# PM_proto_3.net
KiCad netlist of a schematic drawn in EAGLE
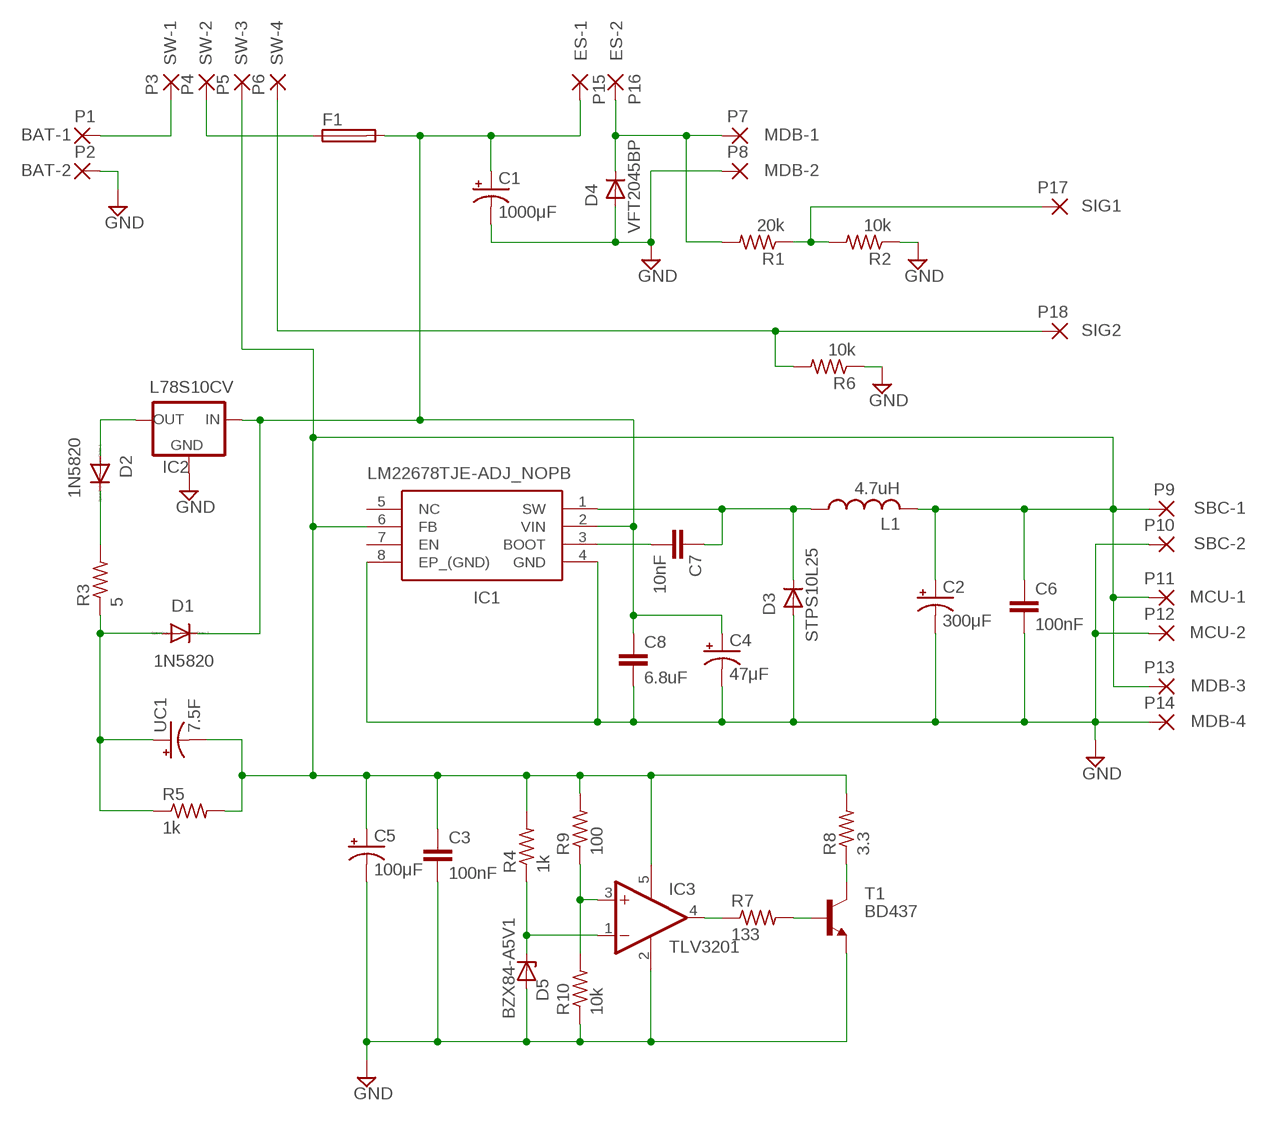
[diagram p0: schematic, sheet 1]

(export (version "E")
  (design (tool "Eeschema 10.0.6"))
  (components
    (comp (ref "C1")
      (value "1000μF")
      (footprint "eagle-import:E7,5-16")
      (libsource (lib "eagle-import") (part "CPOL-USE7.5-16"))
    )
    (comp (ref "C2")
      (value "300μF")
      (footprint "eagle-import:E2,5-6E")
      (libsource (lib "eagle-import") (part "CPOL-USE2,5-6E"))
    )
    (comp (ref "C3")
      (value "100nF")
      (footprint "eagle-import:C025-024X044")
      (libsource (lib "eagle-import") (part "C-EU025-024X044"))
    )
    (comp (ref "C4")
      (value "47μF")
      (footprint "eagle-import:E2,5-6E")
      (libsource (lib "eagle-import") (part "CPOL-USE2,5-6E"))
    )
    (comp (ref "C5")
      (value "100μF")
      (footprint "eagle-import:E2,5-6E")
      (libsource (lib "eagle-import") (part "CPOL-USE2,5-6E"))
    )
    (comp (ref "C6")
      (value "100nF")
      (footprint "eagle-import:C025-024X044")
      (libsource (lib "eagle-import") (part "C-EU025-024X044"))
    )
    (comp (ref "C7")
      (value "10nF")
      (footprint "eagle-import:C025-024X044")
      (libsource (lib "eagle-import") (part "C-EU025-024X044"))
    )
    (comp (ref "C8")
      (value "6.8uF")
      (footprint "eagle-import:C025-024X044")
      (libsource (lib "eagle-import") (part "C-EU025-024X044"))
    )
    (comp (ref "D1")
      (value "1N5820")
      (footprint "eagle-import:DO41-10")
      (libsource (lib "eagle-import") (part "1N4004"))
    )
    (comp (ref "D2")
      (value "1N5820")
      (footprint "eagle-import:DO41-10")
      (libsource (lib "eagle-import") (part "1N4004"))
    )
    (comp (ref "D3")
      (value "STPS10L25")
      (footprint "eagle-import:VFT2045BP")
      (libsource (lib "eagle-import") (part "VFT2045BP"))
    )
    (comp (ref "D4")
      (value "VFT2045BP")
      (footprint "eagle-import:VFT2045BP")
      (libsource (lib "eagle-import") (part "VFT2045BP"))
    )
    (comp (ref "D5")
      (value "BZX84-A5V1")
      (footprint "eagle-import:DO41Z10")
      (libsource (lib "eagle-import") (part "1N4728"))
    )
    (comp (ref "F1")
      (value "0297015FUSE")
      (footprint "eagle-import:0297015HOLDER")
      (libsource (lib "eagle-import") (part "0297015FUSE"))
    )
    (comp (ref "IC1")
      (value "LM22678TJE-ADJ_NOPB")
      (footprint "eagle-import:LM22678TJEADJNOPB")
      (fields
        (field (name "ARROW_PART_NUMBER") "LM22678TJE-ADJ/NOPB")
        (field (name "RS_PART_NUMBER") "1625056")
      )
      (libsource (lib "eagle-import") (part "LM22678TJE-ADJ_NOPB"))
    )
    (comp (ref "IC2")
      (value "L78S10CV")
      (footprint "eagle-import:78XXS")
      (libsource (lib "eagle-import") (part "78XXS"))
    )
    (comp (ref "IC3")
      (value "TLV3201")
      (footprint "eagle-import:DBV-R-PDSO-G5")
      (libsource (lib "eagle-import") (part "TL331"))
    )
    (comp (ref "L1")
      (value "4.7uH")
      (footprint "eagle-import:6000-XXXX-RC")
      (libsource (lib "eagle-import") (part "L-US6000-XXX-RC"))
    )
    (comp (ref "P1")
      (value "BAT-1")
      (footprint "eagle-import:1,6_0,8")
      (libsource (lib "eagle-import") (part "1,6/0,8"))
    )
    (comp (ref "P2")
      (value "BAT-2")
      (footprint "eagle-import:1,6_0,8")
      (libsource (lib "eagle-import") (part "1,6/0,8"))
    )
    (comp (ref "P3")
      (value "SW-1")
      (footprint "eagle-import:1,6_0,8")
      (libsource (lib "eagle-import") (part "1,6/0,8"))
    )
    (comp (ref "P4")
      (value "SW-2")
      (footprint "eagle-import:1,6_0,8")
      (libsource (lib "eagle-import") (part "1,6/0,8"))
    )
    (comp (ref "P5")
      (value "SW-3")
      (footprint "eagle-import:1,6_0,8")
      (libsource (lib "eagle-import") (part "1,6/0,8"))
    )
    (comp (ref "P6")
      (value "SW-4")
      (footprint "eagle-import:1,6_0,8")
      (libsource (lib "eagle-import") (part "1,6/0,8"))
    )
    (comp (ref "P7")
      (value "MDB-1")
      (footprint "eagle-import:1,6_0,8")
      (libsource (lib "eagle-import") (part "1,6/0,8"))
    )
    (comp (ref "P8")
      (value "MDB-2")
      (footprint "eagle-import:1,6_0,8")
      (libsource (lib "eagle-import") (part "1,6/0,8"))
    )
    (comp (ref "P9")
      (value "SBC-1")
      (footprint "eagle-import:1,6_0,8")
      (libsource (lib "eagle-import") (part "1,6/0,8"))
    )
    (comp (ref "P10")
      (value "SBC-2")
      (footprint "eagle-import:1,6_0,8")
      (libsource (lib "eagle-import") (part "1,6/0,8"))
    )
    (comp (ref "P11")
      (value "MCU-1")
      (footprint "eagle-import:1,6_0,8")
      (libsource (lib "eagle-import") (part "1,6/0,8"))
    )
    (comp (ref "P12")
      (value "MCU-2")
      (footprint "eagle-import:1,6_0,8")
      (libsource (lib "eagle-import") (part "1,6/0,8"))
    )
    (comp (ref "P13")
      (value "MDB-3")
      (footprint "eagle-import:1,6_0,8")
      (libsource (lib "eagle-import") (part "1,6/0,8"))
    )
    (comp (ref "P14")
      (value "MDB-4")
      (footprint "eagle-import:1,6_0,8")
      (libsource (lib "eagle-import") (part "1,6/0,8"))
    )
    (comp (ref "P15")
      (value "ES-1")
      (footprint "eagle-import:1,6_0,8")
      (libsource (lib "eagle-import") (part "1,6/0,8"))
    )
    (comp (ref "P16")
      (value "ES-2")
      (footprint "eagle-import:1,6_0,8")
      (libsource (lib "eagle-import") (part "1,6/0,8"))
    )
    (comp (ref "P17")
      (value "SIG1")
      (footprint "eagle-import:1,6_0,8")
      (libsource (lib "eagle-import") (part "1,6/0,8"))
    )
    (comp (ref "P18")
      (value "SIG2")
      (footprint "eagle-import:1,6_0,8")
      (libsource (lib "eagle-import") (part "1,6/0,8"))
    )
    (comp (ref "R1")
      (value "20k")
      (footprint "eagle-import:0204_7")
      (libsource (lib "eagle-import") (part "R-US_0204/7"))
    )
    (comp (ref "R2")
      (value "10k")
      (footprint "eagle-import:0204_7")
      (libsource (lib "eagle-import") (part "R-US_0204/7"))
    )
    (comp (ref "R3")
      (value "5")
      (footprint "eagle-import:TNP10SC10R0FE")
      (libsource (lib "eagle-import") (part "TNP10SC10R0FE"))
    )
    (comp (ref "R4")
      (value "1k")
      (footprint "eagle-import:0204_7")
      (libsource (lib "eagle-import") (part "R-US_0204/7"))
    )
    (comp (ref "R5")
      (value "1k")
      (footprint "eagle-import:0204_7")
      (libsource (lib "eagle-import") (part "R-US_0204/7"))
    )
    (comp (ref "R6")
      (value "10k")
      (footprint "eagle-import:0204_7")
      (libsource (lib "eagle-import") (part "R-US_0204/7"))
    )
    (comp (ref "R7")
      (value "133")
      (footprint "eagle-import:0204_7")
      (libsource (lib "eagle-import") (part "R-US_0204/7"))
    )
    (comp (ref "R8")
      (value "3.3")
      (footprint "eagle-import:0204_7")
      (libsource (lib "eagle-import") (part "R-US_0204/7"))
    )
    (comp (ref "R9")
      (value "100")
      (footprint "eagle-import:0204_7")
      (libsource (lib "eagle-import") (part "R-US_0204/7"))
    )
    (comp (ref "R10")
      (value "10k")
      (footprint "eagle-import:0204_7")
      (libsource (lib "eagle-import") (part "R-US_0204/7"))
    )
    (comp (ref "T1")
      (value "BD437")
      (footprint "eagle-import:TO18")
      (libsource (lib "eagle-import") (part "2N706"))
    )
    (comp (ref "UC1")
      (value "7.5F")
      (footprint "eagle-import:SCMT32D755MRBB0")
      (libsource (lib "eagle-import") (part "SCMT32D755MRBB0"))
    )
  )
  (nets
    (net (code "1") (name "GND") (class "Default")
      (node (ref "C1") (pin "-") (pinfunction "-_-") (pintype "passive"))
      (node (ref "C2") (pin "-") (pinfunction "-_-") (pintype "passive"))
      (node (ref "C3") (pin "2") (pinfunction "2_2") (pintype "passive"))
      (node (ref "C4") (pin "-") (pinfunction "-_-") (pintype "passive"))
      (node (ref "C5") (pin "-") (pinfunction "-_-") (pintype "passive"))
      (node (ref "C6") (pin "2") (pinfunction "2_2") (pintype "passive"))
      (node (ref "C8") (pin "2") (pinfunction "2_2") (pintype "passive"))
      (node (ref "D3") (pin "2") (pinfunction "A_2") (pintype "passive"))
      (node (ref "D4") (pin "2") (pinfunction "A_2") (pintype "passive"))
      (node (ref "D5") (pin "A") (pinfunction "A_A") (pintype "passive"))
      (node (ref "IC1") (pin "4") (pinfunction "GND_4") (pintype "power_in"))
      (node (ref "IC1") (pin "8") (pinfunction "EP_(GND)_8") (pintype "power_in"))
      (node (ref "IC2") (pin "GND") (pinfunction "GND_GND") (pintype "input"))
      (node (ref "IC3") (pin "2") (pinfunction "GND_2") (pintype "power_in"))
      (node (ref "P10") (pin "1") (pinfunction "P_1") (pintype "passive"))
      (node (ref "P12") (pin "1") (pinfunction "P_1") (pintype "passive"))
      (node (ref "P14") (pin "1") (pinfunction "P_1") (pintype "passive"))
      (node (ref "P2") (pin "1") (pinfunction "P_1") (pintype "passive"))
      (node (ref "P8") (pin "1") (pinfunction "P_1") (pintype "passive"))
      (node (ref "R10") (pin "1") (pinfunction "1_1") (pintype "passive"))
      (node (ref "R2") (pin "1") (pinfunction "1_1") (pintype "passive"))
      (node (ref "R6") (pin "1") (pinfunction "1_1") (pintype "passive"))
      (node (ref "T1") (pin "1") (pinfunction "E_1") (pintype "passive"))
    )
    (net (code "2") (name "Net-(D2-PadA)") (class "Default")
      (node (ref "D2") (pin "A") (pinfunction "A_A") (pintype "passive"))
      (node (ref "IC2") (pin "OUT") (pinfunction "OUT_OUT") (pintype "passive"))
    )
    (net (code "3") (name "Net-(D2-PadC)") (class "Default")
      (node (ref "D2") (pin "C") (pinfunction "C_C") (pintype "passive"))
      (node (ref "R3") (pin "2") (pinfunction "2_2") (pintype "passive"))
    )
    (net (code "4") (name "Net-(D3-C)") (class "Default")
      (node (ref "C7") (pin "1") (pinfunction "1_1") (pintype "passive"))
      (node (ref "D3") (pin "1") (pinfunction "C_1") (pintype "passive"))
      (node (ref "IC1") (pin "1") (pinfunction "SW_1") (pintype "power_in"))
      (node (ref "L1") (pin "1") (pinfunction "1_1") (pintype "passive"))
    )
    (net (code "5") (name "Net-(D4-C)") (class "Default")
      (node (ref "D4") (pin "1") (pinfunction "C_1") (pintype "passive"))
      (node (ref "P16") (pin "1") (pinfunction "P_1") (pintype "passive"))
      (node (ref "P7") (pin "1") (pinfunction "P_1") (pintype "passive"))
      (node (ref "R1") (pin "2") (pinfunction "2_2") (pintype "passive"))
    )
    (net (code "6") (name "Net-(IC1-BOOT)") (class "Default")
      (node (ref "C7") (pin "2") (pinfunction "2_2") (pintype "passive"))
      (node (ref "IC1") (pin "3") (pinfunction "BOOT_3") (pintype "bidirectional"))
    )
    (net (code "7") (name "Net-(IC1-FB)") (class "Default")
      (node (ref "C2") (pin "+") (pinfunction "+_+") (pintype "passive"))
      (node (ref "C3") (pin "1") (pinfunction "1_1") (pintype "passive"))
      (node (ref "C5") (pin "+") (pinfunction "+_+") (pintype "passive"))
      (node (ref "C6") (pin "1") (pinfunction "1_1") (pintype "passive"))
      (node (ref "IC1") (pin "6") (pinfunction "FB_6") (pintype "input"))
      (node (ref "IC3") (pin "5") (pinfunction "V+_5") (pintype "power_in"))
      (node (ref "L1") (pin "2") (pinfunction "2_2") (pintype "passive"))
      (node (ref "P11") (pin "1") (pinfunction "P_1") (pintype "passive"))
      (node (ref "P13") (pin "1") (pinfunction "P_1") (pintype "passive"))
      (node (ref "P5") (pin "1") (pinfunction "P_1") (pintype "passive"))
      (node (ref "P9") (pin "1") (pinfunction "P_1") (pintype "passive"))
      (node (ref "R4") (pin "2") (pinfunction "2_2") (pintype "passive"))
      (node (ref "R5") (pin "2") (pinfunction "2_2") (pintype "passive"))
      (node (ref "R8") (pin "2") (pinfunction "2_2") (pintype "passive"))
      (node (ref "R9") (pin "2") (pinfunction "2_2") (pintype "passive"))
      (node (ref "UC1") (pin "2") (pinfunction "-_2") (pintype "passive"))
    )
    (net (code "8") (name "Net-(IC1-VIN)") (class "Default")
      (node (ref "C1") (pin "+") (pinfunction "+_+") (pintype "passive"))
      (node (ref "C4") (pin "+") (pinfunction "+_+") (pintype "passive"))
      (node (ref "C8") (pin "1") (pinfunction "1_1") (pintype "passive"))
      (node (ref "D1") (pin "C") (pinfunction "C_C") (pintype "passive"))
      (node (ref "F1") (pin "3") (pinfunction "2_3") (pintype "passive"))
      (node (ref "F1") (pin "4") (pinfunction "2_4") (pintype "passive"))
      (node (ref "IC1") (pin "2") (pinfunction "VIN_2") (pintype "power_in"))
      (node (ref "IC2") (pin "IN") (pinfunction "IN_IN") (pintype "input"))
      (node (ref "P15") (pin "1") (pinfunction "P_1") (pintype "passive"))
    )
    (net (code "9") (name "Net-(IC3-+IN)") (class "Default")
      (node (ref "IC3") (pin "3") (pinfunction "+IN_3") (pintype "input"))
      (node (ref "R10") (pin "2") (pinfunction "2_2") (pintype "passive"))
      (node (ref "R9") (pin "1") (pinfunction "1_1") (pintype "passive"))
    )
    (net (code "10") (name "Net-(IC3--IN)") (class "Default")
      (node (ref "D5") (pin "C") (pinfunction "C_C") (pintype "passive"))
      (node (ref "IC3") (pin "1") (pinfunction "-IN_1") (pintype "input"))
      (node (ref "R4") (pin "1") (pinfunction "1_1") (pintype "passive"))
    )
    (net (code "11") (name "Net-(IC3-OUT)") (class "Default")
      (node (ref "IC3") (pin "4") (pinfunction "OUT_4") (pintype "output"))
      (node (ref "R7") (pin "1") (pinfunction "1_1") (pintype "passive"))
    )
    (net (code "12") (name "Net-(P1-P)") (class "Default")
      (node (ref "P1") (pin "1") (pinfunction "P_1") (pintype "passive"))
      (node (ref "P3") (pin "1") (pinfunction "P_1") (pintype "passive"))
    )
    (net (code "13") (name "Net-(P4-P)") (class "Default")
      (node (ref "F1") (pin "1") (pinfunction "1_1") (pintype "passive"))
      (node (ref "F1") (pin "2") (pinfunction "1_2") (pintype "passive"))
      (node (ref "P4") (pin "1") (pinfunction "P_1") (pintype "passive"))
    )
    (net (code "14") (name "Net-(P17-P)") (class "Default")
      (node (ref "P17") (pin "1") (pinfunction "P_1") (pintype "passive"))
      (node (ref "R1") (pin "1") (pinfunction "1_1") (pintype "passive"))
      (node (ref "R2") (pin "2") (pinfunction "2_2") (pintype "passive"))
    )
    (net (code "15") (name "Net-(P18-P)") (class "Default")
      (node (ref "P18") (pin "1") (pinfunction "P_1") (pintype "passive"))
      (node (ref "P6") (pin "1") (pinfunction "P_1") (pintype "passive"))
      (node (ref "R6") (pin "2") (pinfunction "2_2") (pintype "passive"))
    )
    (net (code "16") (name "Net-(T1-B)") (class "Default")
      (node (ref "R7") (pin "2") (pinfunction "2_2") (pintype "passive"))
      (node (ref "T1") (pin "2") (pinfunction "B_2") (pintype "passive"))
    )
    (net (code "17") (name "Net-(T1-C)") (class "Default")
      (node (ref "R8") (pin "1") (pinfunction "1_1") (pintype "passive"))
      (node (ref "T1") (pin "3") (pinfunction "C_3") (pintype "passive"))
    )
    (net (code "18") (name "Net-(UC1-+)") (class "Default")
      (node (ref "D1") (pin "A") (pinfunction "A_A") (pintype "passive"))
      (node (ref "R3") (pin "1") (pinfunction "1_1") (pintype "passive"))
      (node (ref "R5") (pin "1") (pinfunction "1_1") (pintype "passive"))
      (node (ref "UC1") (pin "1") (pinfunction "+_1") (pintype "passive"))
    )
    (net (code "19") (name "unconnected-(IC1-EN-Pad7)") (class "Default")
      (node (ref "IC1") (pin "7") (pinfunction "EN_7") (pintype "input"))
    )
    (net (code "20") (name "unconnected-(IC1-NC-Pad5)") (class "Default")
      (node (ref "IC1") (pin "5") (pinfunction "NC_5") (pintype "no_connect"))
    )
  )
)
